# RF_SW.net
KiCad netlist of a schematic drawn in Altium Designer
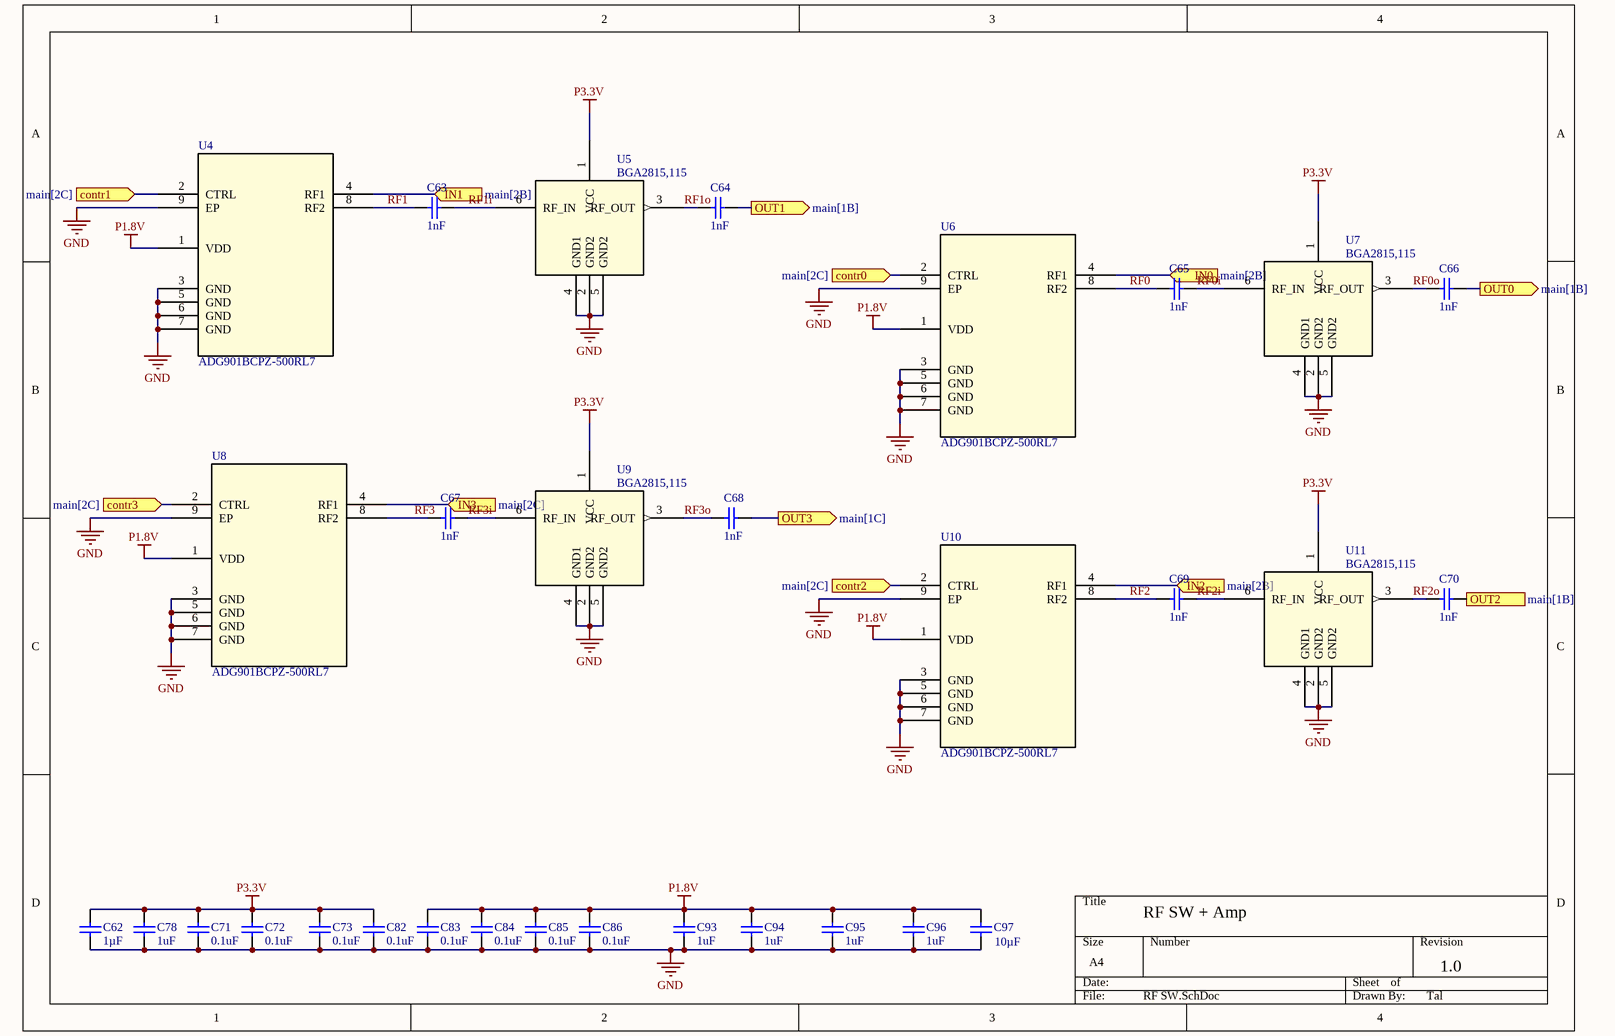
[diagram p0: RF SW.SchDoc]

(export (version "E")
  (design (tool "Eeschema 10.0.6"))
  (components
    (comp (ref "C62")
      (value "1uF 16V")
      (footprint "Landa_PCB:C0603")
      (description "CAP CER 1UF 16V 10% X7R 0603")
      (fields
        (field (name "MANUFACTURER") "TDK Corporation")
        (field (name "MANUFACTURER PART NUMBER") "C1608X7R1C105K")
        (field (name "CAPACITANCE") "1µF")
      )
      (libsource (lib "L_SCH_C") (part "CAP CER 1uF 16V 10% X7R 0603"))
    )
    (comp (ref "C63")
      (value "1nF 25V")
      (footprint "Landa_PCB:C0402")
      (description "CAP CER 1nF 25V 10% X7R 0402")
      (fields
        (field (name "MANUFACTURER PART NUMBER") "C1005X7R1E333K")
        (field (name "MANUFACTURER") "TDK Corporation")
        (field (name "CAPACITANCE") "1nF")
      )
      (libsource (lib "L_SCH_C") (part "CAP CER 33nF 25V 10% X7R 0402"))
    )
    (comp (ref "C64")
      (value "1nF 25V")
      (footprint "Landa_PCB:C0402")
      (description "CAP CER 1nF 25V 10% X7R 0402")
      (fields
        (field (name "MANUFACTURER PART NUMBER") "C1005X7R1E333K")
        (field (name "MANUFACTURER") "TDK Corporation")
        (field (name "CAPACITANCE") "1nF")
      )
      (libsource (lib "L_SCH_C") (part "CAP CER 33nF 25V 10% X7R 0402"))
    )
    (comp (ref "C65")
      (value "1nF 25V")
      (footprint "Landa_PCB:C0402")
      (description "CAP CER 1nF 25V 10% X7R 0402")
      (fields
        (field (name "MANUFACTURER PART NUMBER") "C1005X7R1E333K")
        (field (name "MANUFACTURER") "TDK Corporation")
        (field (name "CAPACITANCE") "1nF")
      )
      (libsource (lib "L_SCH_C") (part "CAP CER 33nF 25V 10% X7R 0402"))
    )
    (comp (ref "C66")
      (value "1nF 25V")
      (footprint "Landa_PCB:C0402")
      (description "CAP CER 1nF 25V 10% X7R 0402")
      (fields
        (field (name "MANUFACTURER PART NUMBER") "C1005X7R1E333K")
        (field (name "MANUFACTURER") "TDK Corporation")
        (field (name "CAPACITANCE") "1nF")
      )
      (libsource (lib "L_SCH_C") (part "CAP CER 33nF 25V 10% X7R 0402"))
    )
    (comp (ref "C67")
      (value "1nF 25V")
      (footprint "Landa_PCB:C0402")
      (description "CAP CER 1nF 25V 10% X7R 0402")
      (fields
        (field (name "MANUFACTURER PART NUMBER") "C1005X7R1E333K")
        (field (name "MANUFACTURER") "TDK Corporation")
        (field (name "CAPACITANCE") "1nF")
      )
      (libsource (lib "L_SCH_C") (part "CAP CER 33nF 25V 10% X7R 0402"))
    )
    (comp (ref "C68")
      (value "1nF 25V")
      (footprint "Landa_PCB:C0402")
      (description "CAP CER 1nF 25V 10% X7R 0402")
      (fields
        (field (name "MANUFACTURER PART NUMBER") "C1005X7R1E333K")
        (field (name "MANUFACTURER") "TDK Corporation")
        (field (name "CAPACITANCE") "1nF")
      )
      (libsource (lib "L_SCH_C") (part "CAP CER 33nF 25V 10% X7R 0402"))
    )
    (comp (ref "C69")
      (value "1nF 25V")
      (footprint "Landa_PCB:C0402")
      (description "CAP CER 1nF 25V 10% X7R 0402")
      (fields
        (field (name "MANUFACTURER PART NUMBER") "C1005X7R1E333K")
        (field (name "MANUFACTURER") "TDK Corporation")
        (field (name "CAPACITANCE") "1nF")
      )
      (libsource (lib "L_SCH_C") (part "CAP CER 33nF 25V 10% X7R 0402"))
    )
    (comp (ref "C70")
      (value "1nF 25V")
      (footprint "Landa_PCB:C0402")
      (description "CAP CER 1nF 25V 10% X7R 0402")
      (fields
        (field (name "MANUFACTURER PART NUMBER") "C1005X7R1E333K")
        (field (name "MANUFACTURER") "TDK Corporation")
        (field (name "CAPACITANCE") "1nF")
      )
      (libsource (lib "L_SCH_C") (part "CAP CER 33nF 25V 10% X7R 0402"))
    )
    (comp (ref "C71")
      (value "0.1uF 50V")
      (footprint "Landa_PCB:C0402")
      (description "CAP CER 0.1uF 50V NP0 0402")
      (fields
        (field (name "MANUFACTURER PART NUMBER") "C1005C0G1H6R8D")
        (field (name "MANUFACTURER") "TDK Corporation")
        (field (name "CAPACITANCE") "0.1uF")
      )
      (libsource (lib "L_SCH_C") (part "CAP CER 6.8pF 50V NP0 0402"))
    )
    (comp (ref "C72")
      (value "0.1uF 50V")
      (footprint "Landa_PCB:C0402")
      (description "CAP CER 0.1uF 50V NP0 0402")
      (fields
        (field (name "MANUFACTURER PART NUMBER") "C1005C0G1H6R8D")
        (field (name "MANUFACTURER") "TDK Corporation")
        (field (name "CAPACITANCE") "0.1uF")
      )
      (libsource (lib "L_SCH_C") (part "CAP CER 6.8pF 50V NP0 0402"))
    )
    (comp (ref "C73")
      (value "0.1uF 50V")
      (footprint "Landa_PCB:C0402")
      (description "CAP CER 0.1uF 50V NP0 0402")
      (fields
        (field (name "MANUFACTURER PART NUMBER") "C1005C0G1H6R8D")
        (field (name "MANUFACTURER") "TDK Corporation")
        (field (name "CAPACITANCE") "0.1uF")
      )
      (libsource (lib "L_SCH_C") (part "CAP CER 6.8pF 50V NP0 0402"))
    )
    (comp (ref "C78")
      (value "1uF 25V")
      (footprint "Landa_PCB:C0402")
      (description "CAP CER 1uF 25V X5R 0402")
      (fields
        (field (name "MANUFACTURER PART NUMBER") "C1005C0G1H6R8D")
        (field (name "MANUFACTURER") "TDK Corporation")
        (field (name "CAPACITANCE") "1uF")
      )
      (libsource (lib "L_SCH_C") (part "CAP CER 6.8pF 50V NP0 0402"))
    )
    (comp (ref "C82")
      (value "0.1uF 50V")
      (footprint "Landa_PCB:C0402")
      (description "CAP CER 0.1uF 50V NP0 0402")
      (fields
        (field (name "MANUFACTURER PART NUMBER") "C1005C0G1H6R8D")
        (field (name "MANUFACTURER") "TDK Corporation")
        (field (name "CAPACITANCE") "0.1uF")
      )
      (libsource (lib "L_SCH_C") (part "CAP CER 6.8pF 50V NP0 0402"))
    )
    (comp (ref "C83")
      (value "0.1uF 50V")
      (footprint "Landa_PCB:C0402")
      (description "CAP CER 0.1uF 50V NP0 0402")
      (fields
        (field (name "MANUFACTURER PART NUMBER") "C1005C0G1H6R8D")
        (field (name "MANUFACTURER") "TDK Corporation")
        (field (name "CAPACITANCE") "0.1uF")
      )
      (libsource (lib "L_SCH_C") (part "CAP CER 6.8pF 50V NP0 0402"))
    )
    (comp (ref "C84")
      (value "0.1uF 50V")
      (footprint "Landa_PCB:C0402")
      (description "CAP CER 0.1uF 50V NP0 0402")
      (fields
        (field (name "MANUFACTURER PART NUMBER") "C1005C0G1H6R8D")
        (field (name "MANUFACTURER") "TDK Corporation")
        (field (name "CAPACITANCE") "0.1uF")
      )
      (libsource (lib "L_SCH_C") (part "CAP CER 6.8pF 50V NP0 0402"))
    )
    (comp (ref "C85")
      (value "0.1uF 50V")
      (footprint "Landa_PCB:C0402")
      (description "CAP CER 0.1uF 50V NP0 0402")
      (fields
        (field (name "MANUFACTURER PART NUMBER") "C1005C0G1H6R8D")
        (field (name "MANUFACTURER") "TDK Corporation")
        (field (name "CAPACITANCE") "0.1uF")
      )
      (libsource (lib "L_SCH_C") (part "CAP CER 6.8pF 50V NP0 0402"))
    )
    (comp (ref "C86")
      (value "0.1uF 50V")
      (footprint "Landa_PCB:C0402")
      (description "CAP CER 0.1uF 50V NP0 0402")
      (fields
        (field (name "MANUFACTURER PART NUMBER") "C1005C0G1H6R8D")
        (field (name "MANUFACTURER") "TDK Corporation")
        (field (name "CAPACITANCE") "0.1uF")
      )
      (libsource (lib "L_SCH_C") (part "CAP CER 6.8pF 50V NP0 0402"))
    )
    (comp (ref "C93")
      (value "1uF 25V")
      (footprint "Landa_PCB:C0402")
      (description "CAP CER 1uF 25V X5R 0402")
      (fields
        (field (name "MANUFACTURER PART NUMBER") "C1005C0G1H6R8D")
        (field (name "MANUFACTURER") "TDK Corporation")
        (field (name "CAPACITANCE") "1uF")
      )
      (libsource (lib "L_SCH_C") (part "CAP CER 6.8pF 50V NP0 0402"))
    )
    (comp (ref "C94")
      (value "1uF 25V")
      (footprint "Landa_PCB:C0402")
      (description "CAP CER 1uF 25V X5R 0402")
      (fields
        (field (name "MANUFACTURER PART NUMBER") "C1005C0G1H6R8D")
        (field (name "MANUFACTURER") "TDK Corporation")
        (field (name "CAPACITANCE") "1uF")
      )
      (libsource (lib "L_SCH_C") (part "CAP CER 6.8pF 50V NP0 0402"))
    )
    (comp (ref "C95")
      (value "1uF 25V")
      (footprint "Landa_PCB:C0402")
      (description "CAP CER 1uF 25V X5R 0402")
      (fields
        (field (name "MANUFACTURER PART NUMBER") "C1005C0G1H6R8D")
        (field (name "MANUFACTURER") "TDK Corporation")
        (field (name "CAPACITANCE") "1uF")
      )
      (libsource (lib "L_SCH_C") (part "CAP CER 6.8pF 50V NP0 0402"))
    )
    (comp (ref "C96")
      (value "1uF 25V")
      (footprint "Landa_PCB:C0402")
      (description "CAP CER 1uF 25V X5R 0402")
      (fields
        (field (name "MANUFACTURER PART NUMBER") "C1005C0G1H6R8D")
        (field (name "MANUFACTURER") "TDK Corporation")
        (field (name "CAPACITANCE") "1uF")
      )
      (libsource (lib "L_SCH_C") (part "CAP CER 6.8pF 50V NP0 0402"))
    )
    (comp (ref "C97")
      (value "10uF 25V")
      (footprint "Landa_PCB:C0603")
      (description "CAP CER 10UF 25V 10% X5R 0603")
      (fields
        (field (name "MANUFACTURER PART NUMBER") "C1608X5R1A106K")
        (field (name "MANUFACTURER") "TDK Corporation")
        (field (name "CAPACITANCE") "10µF")
      )
      (libsource (lib "L_SCH_C") (part "CAP CER 10uF 10V 10% X5R 0603"))
    )
    (comp (ref "U4")
      (value "ADG901BCPZ-500RL7")
      (footprint "CP_8_2_ADI")
      (description "No Description Available")
      (fields (field (name "COPYRIGHT") "Copyright (C) 2023 Ultra Librarian. All rights reserved."))
      (libsource (lib "ADG901BCPZ-500RL7") (part "ADG901BCPZ-500RL7"))
    )
    (comp (ref "U5")
      (value "BGA2815,115")
      (footprint "SOT_2815,115_NXP")
      (description "No Description Available")
      (fields (field (name "COPYRIGHT") "Copyright (C) 2023 Ultra Librarian. All rights reserved."))
      (libsource (lib "BGA2815,115") (part "BGA2815,115"))
    )
    (comp (ref "U6")
      (value "ADG901BCPZ-500RL7")
      (footprint "CP_8_2_ADI")
      (description "No Description Available")
      (fields (field (name "COPYRIGHT") "Copyright (C) 2023 Ultra Librarian. All rights reserved."))
      (libsource (lib "ADG901BCPZ-500RL7") (part "ADG901BCPZ-500RL7"))
    )
    (comp (ref "U7")
      (value "BGA2815,115")
      (footprint "SOT_2815,115_NXP")
      (description "No Description Available")
      (fields (field (name "COPYRIGHT") "Copyright (C) 2023 Ultra Librarian. All rights reserved."))
      (libsource (lib "BGA2815,115") (part "BGA2815,115"))
    )
    (comp (ref "U8")
      (value "ADG901BCPZ-500RL7")
      (footprint "CP_8_2_ADI")
      (description "No Description Available")
      (fields (field (name "COPYRIGHT") "Copyright (C) 2023 Ultra Librarian. All rights reserved."))
      (libsource (lib "ADG901BCPZ-500RL7") (part "ADG901BCPZ-500RL7"))
    )
    (comp (ref "U9")
      (value "BGA2815,115")
      (footprint "SOT_2815,115_NXP")
      (description "No Description Available")
      (fields (field (name "COPYRIGHT") "Copyright (C) 2023 Ultra Librarian. All rights reserved."))
      (libsource (lib "BGA2815,115") (part "BGA2815,115"))
    )
    (comp (ref "U10")
      (value "ADG901BCPZ-500RL7")
      (footprint "CP_8_2_ADI")
      (description "No Description Available")
      (fields (field (name "COPYRIGHT") "Copyright (C) 2023 Ultra Librarian. All rights reserved."))
      (libsource (lib "ADG901BCPZ-500RL7") (part "ADG901BCPZ-500RL7"))
    )
    (comp (ref "U11")
      (value "BGA2815,115")
      (footprint "SOT_2815,115_NXP")
      (description "No Description Available")
      (fields (field (name "COPYRIGHT") "Copyright (C) 2023 Ultra Librarian. All rights reserved."))
      (libsource (lib "BGA2815,115") (part "BGA2815,115"))
    )
  )
  (nets
    (net (code "1") (name "/IN0") (class "Default")
      (node (ref "U6") (pin "4") (pinfunction "RF1_4") (pintype "passive"))
    )
    (net (code "2") (name "/IN1") (class "Default")
      (node (ref "U4") (pin "4") (pinfunction "RF1_4") (pintype "passive"))
    )
    (net (code "3") (name "/IN2") (class "Default")
      (node (ref "U10") (pin "4") (pinfunction "RF1_4") (pintype "passive"))
    )
    (net (code "4") (name "/IN3") (class "Default")
      (node (ref "U8") (pin "4") (pinfunction "RF1_4") (pintype "passive"))
    )
    (net (code "5") (name "/OUT0") (class "Default")
      (node (ref "C66") (pin "2") (pinfunction "2_2") (pintype "passive"))
    )
    (net (code "6") (name "/OUT1") (class "Default")
      (node (ref "C64") (pin "2") (pinfunction "2_2") (pintype "passive"))
    )
    (net (code "7") (name "/OUT2") (class "Default")
      (node (ref "C70") (pin "2") (pinfunction "2_2") (pintype "passive"))
    )
    (net (code "8") (name "/OUT3") (class "Default")
      (node (ref "C68") (pin "2") (pinfunction "2_2") (pintype "passive"))
    )
    (net (code "9") (name "/RF0") (class "Default")
      (node (ref "C65") (pin "1") (pinfunction "1_1") (pintype "passive"))
      (node (ref "U6") (pin "8") (pinfunction "RF2_8") (pintype "passive"))
    )
    (net (code "10") (name "/RF0i") (class "Default")
      (node (ref "C65") (pin "2") (pinfunction "2_2") (pintype "passive"))
      (node (ref "U7") (pin "6") (pinfunction "RF_IN_6") (pintype "passive"))
    )
    (net (code "11") (name "/RF0o") (class "Default")
      (node (ref "C66") (pin "1") (pinfunction "1_1") (pintype "passive"))
      (node (ref "U7") (pin "3") (pinfunction "RF_OUT_3") (pintype "output"))
    )
    (net (code "12") (name "/RF1") (class "Default")
      (node (ref "C63") (pin "1") (pinfunction "1_1") (pintype "passive"))
      (node (ref "U4") (pin "8") (pinfunction "RF2_8") (pintype "passive"))
    )
    (net (code "13") (name "/RF1i") (class "Default")
      (node (ref "C63") (pin "2") (pinfunction "2_2") (pintype "passive"))
      (node (ref "U5") (pin "6") (pinfunction "RF_IN_6") (pintype "passive"))
    )
    (net (code "14") (name "/RF1o") (class "Default")
      (node (ref "C64") (pin "1") (pinfunction "1_1") (pintype "passive"))
      (node (ref "U5") (pin "3") (pinfunction "RF_OUT_3") (pintype "output"))
    )
    (net (code "15") (name "/RF2") (class "Default")
      (node (ref "C69") (pin "1") (pinfunction "1_1") (pintype "passive"))
      (node (ref "U10") (pin "8") (pinfunction "RF2_8") (pintype "passive"))
    )
    (net (code "16") (name "/RF2i") (class "Default")
      (node (ref "C69") (pin "2") (pinfunction "2_2") (pintype "passive"))
      (node (ref "U11") (pin "6") (pinfunction "RF_IN_6") (pintype "passive"))
    )
    (net (code "17") (name "/RF2o") (class "Default")
      (node (ref "C70") (pin "1") (pinfunction "1_1") (pintype "passive"))
      (node (ref "U11") (pin "3") (pinfunction "RF_OUT_3") (pintype "output"))
    )
    (net (code "18") (name "/RF3") (class "Default")
      (node (ref "C67") (pin "1") (pinfunction "1_1") (pintype "passive"))
      (node (ref "U8") (pin "8") (pinfunction "RF2_8") (pintype "passive"))
    )
    (net (code "19") (name "/RF3i") (class "Default")
      (node (ref "C67") (pin "2") (pinfunction "2_2") (pintype "passive"))
      (node (ref "U9") (pin "6") (pinfunction "RF_IN_6") (pintype "passive"))
    )
    (net (code "20") (name "/RF3o") (class "Default")
      (node (ref "C68") (pin "1") (pinfunction "1_1") (pintype "passive"))
      (node (ref "U9") (pin "3") (pinfunction "RF_OUT_3") (pintype "output"))
    )
    (net (code "21") (name "/contr0") (class "Default")
      (node (ref "U6") (pin "2") (pinfunction "CTRL_2") (pintype "passive"))
    )
    (net (code "22") (name "/contr1") (class "Default")
      (node (ref "U4") (pin "2") (pinfunction "CTRL_2") (pintype "passive"))
    )
    (net (code "23") (name "/contr2") (class "Default")
      (node (ref "U10") (pin "2") (pinfunction "CTRL_2") (pintype "passive"))
    )
    (net (code "24") (name "/contr3") (class "Default")
      (node (ref "U8") (pin "2") (pinfunction "CTRL_2") (pintype "passive"))
    )
    (net (code "25") (name "GND") (class "Default")
      (node (ref "C62") (pin "1") (pinfunction "1_1") (pintype "passive"))
      (node (ref "C71") (pin "1") (pinfunction "1_1") (pintype "passive"))
      (node (ref "C72") (pin "1") (pinfunction "1_1") (pintype "passive"))
      (node (ref "C73") (pin "1") (pinfunction "1_1") (pintype "passive"))
      (node (ref "C78") (pin "1") (pinfunction "1_1") (pintype "passive"))
      (node (ref "C82") (pin "1") (pinfunction "1_1") (pintype "passive"))
      (node (ref "C83") (pin "1") (pinfunction "1_1") (pintype "passive"))
      (node (ref "C84") (pin "1") (pinfunction "1_1") (pintype "passive"))
      (node (ref "C85") (pin "1") (pinfunction "1_1") (pintype "passive"))
      (node (ref "C86") (pin "1") (pinfunction "1_1") (pintype "passive"))
      (node (ref "C93") (pin "1") (pinfunction "1_1") (pintype "passive"))
      (node (ref "C94") (pin "1") (pinfunction "1_1") (pintype "passive"))
      (node (ref "C95") (pin "1") (pinfunction "1_1") (pintype "passive"))
      (node (ref "C96") (pin "1") (pinfunction "1_1") (pintype "passive"))
      (node (ref "C97") (pin "1") (pinfunction "1_1") (pintype "passive"))
      (node (ref "U10") (pin "3") (pinfunction "GND_3") (pintype "passive"))
      (node (ref "U10") (pin "5") (pinfunction "GND_5") (pintype "passive"))
      (node (ref "U10") (pin "6") (pinfunction "GND_6") (pintype "passive"))
      (node (ref "U10") (pin "7") (pinfunction "GND_7") (pintype "passive"))
      (node (ref "U10") (pin "9") (pinfunction "EP_9") (pintype "passive"))
      (node (ref "U11") (pin "2") (pinfunction "GND2_2") (pintype "passive"))
      (node (ref "U11") (pin "4") (pinfunction "GND1_4") (pintype "passive"))
      (node (ref "U11") (pin "5") (pinfunction "GND2_5") (pintype "passive"))
      (node (ref "U4") (pin "3") (pinfunction "GND_3") (pintype "passive"))
      (node (ref "U4") (pin "5") (pinfunction "GND_5") (pintype "passive"))
      (node (ref "U4") (pin "6") (pinfunction "GND_6") (pintype "passive"))
      (node (ref "U4") (pin "7") (pinfunction "GND_7") (pintype "passive"))
      (node (ref "U4") (pin "9") (pinfunction "EP_9") (pintype "passive"))
      (node (ref "U5") (pin "2") (pinfunction "GND2_2") (pintype "passive"))
      (node (ref "U5") (pin "4") (pinfunction "GND1_4") (pintype "passive"))
      (node (ref "U5") (pin "5") (pinfunction "GND2_5") (pintype "passive"))
      (node (ref "U6") (pin "3") (pinfunction "GND_3") (pintype "passive"))
      (node (ref "U6") (pin "5") (pinfunction "GND_5") (pintype "passive"))
      (node (ref "U6") (pin "6") (pinfunction "GND_6") (pintype "passive"))
      (node (ref "U6") (pin "7") (pinfunction "GND_7") (pintype "passive"))
      (node (ref "U6") (pin "9") (pinfunction "EP_9") (pintype "passive"))
      (node (ref "U7") (pin "2") (pinfunction "GND2_2") (pintype "passive"))
      (node (ref "U7") (pin "4") (pinfunction "GND1_4") (pintype "passive"))
      (node (ref "U7") (pin "5") (pinfunction "GND2_5") (pintype "passive"))
      (node (ref "U8") (pin "3") (pinfunction "GND_3") (pintype "passive"))
      (node (ref "U8") (pin "5") (pinfunction "GND_5") (pintype "passive"))
      (node (ref "U8") (pin "6") (pinfunction "GND_6") (pintype "passive"))
      (node (ref "U8") (pin "7") (pinfunction "GND_7") (pintype "passive"))
      (node (ref "U8") (pin "9") (pinfunction "EP_9") (pintype "passive"))
      (node (ref "U9") (pin "2") (pinfunction "GND2_2") (pintype "passive"))
      (node (ref "U9") (pin "4") (pinfunction "GND1_4") (pintype "passive"))
      (node (ref "U9") (pin "5") (pinfunction "GND2_5") (pintype "passive"))
    )
    (net (code "26") (name "P1.8V") (class "Default")
      (node (ref "C83") (pin "2") (pinfunction "2_2") (pintype "passive"))
      (node (ref "C84") (pin "2") (pinfunction "2_2") (pintype "passive"))
      (node (ref "C85") (pin "2") (pinfunction "2_2") (pintype "passive"))
      (node (ref "C86") (pin "2") (pinfunction "2_2") (pintype "passive"))
      (node (ref "C93") (pin "2") (pinfunction "2_2") (pintype "passive"))
      (node (ref "C94") (pin "2") (pinfunction "2_2") (pintype "passive"))
      (node (ref "C95") (pin "2") (pinfunction "2_2") (pintype "passive"))
      (node (ref "C96") (pin "2") (pinfunction "2_2") (pintype "passive"))
      (node (ref "C97") (pin "2") (pinfunction "2_2") (pintype "passive"))
      (node (ref "U10") (pin "1") (pinfunction "VDD_1") (pintype "power_in"))
      (node (ref "U4") (pin "1") (pinfunction "VDD_1") (pintype "power_in"))
      (node (ref "U6") (pin "1") (pinfunction "VDD_1") (pintype "power_in"))
      (node (ref "U8") (pin "1") (pinfunction "VDD_1") (pintype "power_in"))
    )
    (net (code "27") (name "P3.3V") (class "Default")
      (node (ref "C62") (pin "2") (pinfunction "2_2") (pintype "passive"))
      (node (ref "C71") (pin "2") (pinfunction "2_2") (pintype "passive"))
      (node (ref "C72") (pin "2") (pinfunction "2_2") (pintype "passive"))
      (node (ref "C73") (pin "2") (pinfunction "2_2") (pintype "passive"))
      (node (ref "C78") (pin "2") (pinfunction "2_2") (pintype "passive"))
      (node (ref "C82") (pin "2") (pinfunction "2_2") (pintype "passive"))
      (node (ref "U11") (pin "1") (pinfunction "VCC_1") (pintype "power_in"))
      (node (ref "U5") (pin "1") (pinfunction "VCC_1") (pintype "power_in"))
      (node (ref "U7") (pin "1") (pinfunction "VCC_1") (pintype "power_in"))
      (node (ref "U9") (pin "1") (pinfunction "VCC_1") (pintype "power_in"))
    )
  )
)
